# SCH_06_Analog_Mux.net
KiCad netlist of a schematic drawn in Altium Designer
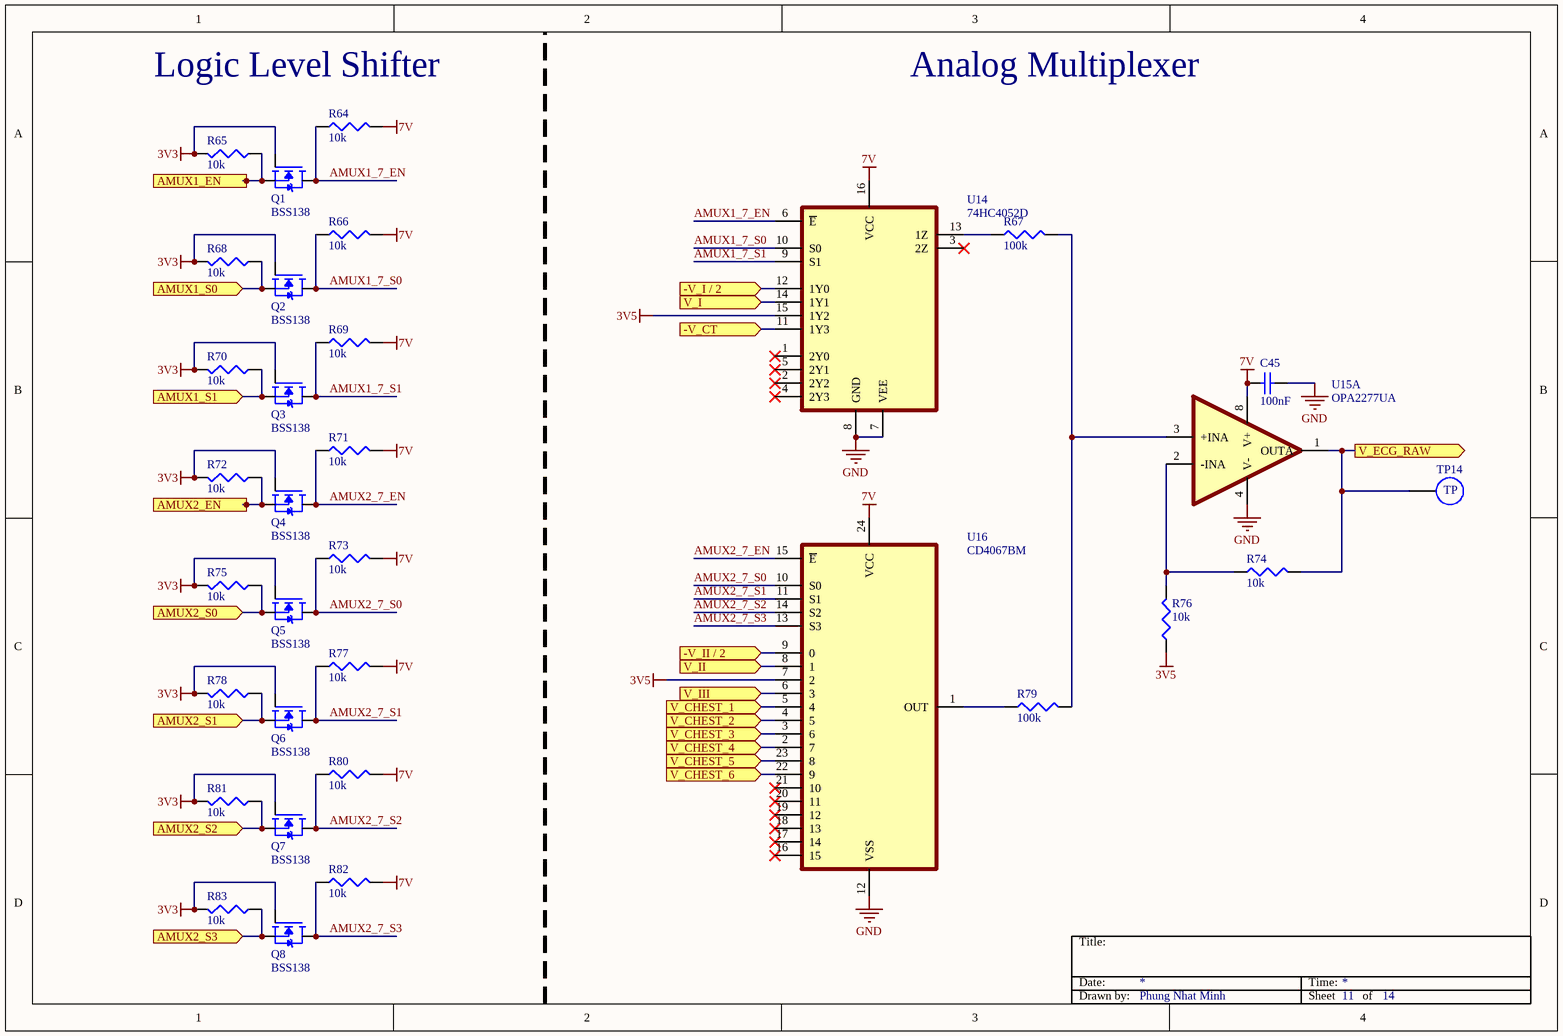
[diagram p0: SCH_06_Analog_Mux.SchDoc]

(export (version "E")
  (design (tool "Eeschema 10.0.6"))
  (components
    (comp (ref "C45")
      (value "100nF")
      (footprint "WCAP-CSGP_0603_L1.6W0.8H0.8_Reflow")
      (description "WCAP-CSGP Multilayer Ceramic Chip Capacitor, General Purpose, size 0603, X7R, 100nF, 50VDC")
      (fields
        (field (name "MANUFACTURER PART NUMBER") "885012206095")
        (field (name "MANUFACTURER") "Wurth Elektronik")
      )
      (libsource (lib "Altium_WCAP-CSGP (rev24b)") (part "885012206095"))
    )
    (comp (ref "Q1")
      (value "BSS138")
      (footprint "SOT95P240X111-3N")
      (description "N-Channel 50V 220mA (Ta) 360mW (Ta) Surface Mount SOT-23-3")
      (fields (field (name "MF") "ON Semiconductor"))
      (libsource (lib "BSS138") (part "BSS138"))
    )
    (comp (ref "Q2")
      (value "BSS138")
      (footprint "SOT95P240X111-3N")
      (description "N-Channel 50V 220mA (Ta) 360mW (Ta) Surface Mount SOT-23-3")
      (fields (field (name "MF") "ON Semiconductor"))
      (libsource (lib "BSS138") (part "BSS138"))
    )
    (comp (ref "Q3")
      (value "BSS138")
      (footprint "SOT95P240X111-3N")
      (description "N-Channel 50V 220mA (Ta) 360mW (Ta) Surface Mount SOT-23-3")
      (fields (field (name "MF") "ON Semiconductor"))
      (libsource (lib "BSS138") (part "BSS138"))
    )
    (comp (ref "Q4")
      (value "BSS138")
      (footprint "SOT95P240X111-3N")
      (description "N-Channel 50V 220mA (Ta) 360mW (Ta) Surface Mount SOT-23-3")
      (fields (field (name "MF") "ON Semiconductor"))
      (libsource (lib "BSS138") (part "BSS138"))
    )
    (comp (ref "Q5")
      (value "BSS138")
      (footprint "SOT95P240X111-3N")
      (description "N-Channel 50V 220mA (Ta) 360mW (Ta) Surface Mount SOT-23-3")
      (fields (field (name "MF") "ON Semiconductor"))
      (libsource (lib "BSS138") (part "BSS138"))
    )
    (comp (ref "Q6")
      (value "BSS138")
      (footprint "SOT95P240X111-3N")
      (description "N-Channel 50V 220mA (Ta) 360mW (Ta) Surface Mount SOT-23-3")
      (fields (field (name "MF") "ON Semiconductor"))
      (libsource (lib "BSS138") (part "BSS138"))
    )
    (comp (ref "Q7")
      (value "BSS138")
      (footprint "SOT95P240X111-3N")
      (description "N-Channel 50V 220mA (Ta) 360mW (Ta) Surface Mount SOT-23-3")
      (fields (field (name "MF") "ON Semiconductor"))
      (libsource (lib "BSS138") (part "BSS138"))
    )
    (comp (ref "Q8")
      (value "BSS138")
      (footprint "SOT95P240X111-3N")
      (description "N-Channel 50V 220mA (Ta) 360mW (Ta) Surface Mount SOT-23-3")
      (fields (field (name "MF") "ON Semiconductor"))
      (libsource (lib "BSS138") (part "BSS138"))
    )
    (comp (ref "R64")
      (value "10k")
      (footprint "WRIS-PSMB_0603_L1.6W0.8H0.35")
      (description "WRIS-PSMB Metal Plate Resistor, SMT, size 0603, 0.33W, 5mΩ, +/-1%")
      (fields
        (field (name "MANUFACTURER PART NUMBER") "580060716001")
        (field (name "MANUFACTURER") "Wurth Elektronik")
      )
      (libsource (lib "Altium_WRIS-PSMB (rev22a)") (part "580060716001"))
    )
    (comp (ref "R65")
      (value "10k")
      (footprint "WRIS-PSMB_0603_L1.6W0.8H0.35")
      (description "WRIS-PSMB Metal Plate Resistor, SMT, size 0603, 0.33W, 5mΩ, +/-1%")
      (fields
        (field (name "MANUFACTURER PART NUMBER") "580060716001")
        (field (name "MANUFACTURER") "Wurth Elektronik")
      )
      (libsource (lib "Altium_WRIS-PSMB (rev22a)") (part "580060716001"))
    )
    (comp (ref "R66")
      (value "10k")
      (footprint "WRIS-PSMB_0603_L1.6W0.8H0.35")
      (description "WRIS-PSMB Metal Plate Resistor, SMT, size 0603, 0.33W, 5mΩ, +/-1%")
      (fields
        (field (name "MANUFACTURER PART NUMBER") "580060716001")
        (field (name "MANUFACTURER") "Wurth Elektronik")
      )
      (libsource (lib "Altium_WRIS-PSMB (rev22a)") (part "580060716001"))
    )
    (comp (ref "R67")
      (value "100k")
      (footprint "WRIS-PSMB_0603_L1.6W0.8H0.35")
      (description "WRIS-PSMB Metal Plate Resistor, SMT, size 0603, 0.33W, 5mΩ, +/-1%")
      (fields
        (field (name "MANUFACTURER PART NUMBER") "580060716001")
        (field (name "MANUFACTURER") "Wurth Elektronik")
      )
      (libsource (lib "Altium_WRIS-PSMB (rev22a)") (part "580060716001"))
    )
    (comp (ref "R68")
      (value "10k")
      (footprint "WRIS-PSMB_0603_L1.6W0.8H0.35")
      (description "WRIS-PSMB Metal Plate Resistor, SMT, size 0603, 0.33W, 5mΩ, +/-1%")
      (fields
        (field (name "MANUFACTURER PART NUMBER") "580060716001")
        (field (name "MANUFACTURER") "Wurth Elektronik")
      )
      (libsource (lib "Altium_WRIS-PSMB (rev22a)") (part "580060716001"))
    )
    (comp (ref "R69")
      (value "10k")
      (footprint "WRIS-PSMB_0603_L1.6W0.8H0.35")
      (description "WRIS-PSMB Metal Plate Resistor, SMT, size 0603, 0.33W, 5mΩ, +/-1%")
      (fields
        (field (name "MANUFACTURER PART NUMBER") "580060716001")
        (field (name "MANUFACTURER") "Wurth Elektronik")
      )
      (libsource (lib "Altium_WRIS-PSMB (rev22a)") (part "580060716001"))
    )
    (comp (ref "R70")
      (value "10k")
      (footprint "WRIS-PSMB_0603_L1.6W0.8H0.35")
      (description "WRIS-PSMB Metal Plate Resistor, SMT, size 0603, 0.33W, 5mΩ, +/-1%")
      (fields
        (field (name "MANUFACTURER PART NUMBER") "580060716001")
        (field (name "MANUFACTURER") "Wurth Elektronik")
      )
      (libsource (lib "Altium_WRIS-PSMB (rev22a)") (part "580060716001"))
    )
    (comp (ref "R71")
      (value "10k")
      (footprint "WRIS-PSMB_0603_L1.6W0.8H0.35")
      (description "WRIS-PSMB Metal Plate Resistor, SMT, size 0603, 0.33W, 5mΩ, +/-1%")
      (fields
        (field (name "MANUFACTURER PART NUMBER") "580060716001")
        (field (name "MANUFACTURER") "Wurth Elektronik")
      )
      (libsource (lib "Altium_WRIS-PSMB (rev22a)") (part "580060716001"))
    )
    (comp (ref "R72")
      (value "10k")
      (footprint "WRIS-PSMB_0603_L1.6W0.8H0.35")
      (description "WRIS-PSMB Metal Plate Resistor, SMT, size 0603, 0.33W, 5mΩ, +/-1%")
      (fields
        (field (name "MANUFACTURER PART NUMBER") "580060716001")
        (field (name "MANUFACTURER") "Wurth Elektronik")
      )
      (libsource (lib "Altium_WRIS-PSMB (rev22a)") (part "580060716001"))
    )
    (comp (ref "R73")
      (value "10k")
      (footprint "WRIS-PSMB_0603_L1.6W0.8H0.35")
      (description "WRIS-PSMB Metal Plate Resistor, SMT, size 0603, 0.33W, 5mΩ, +/-1%")
      (fields
        (field (name "MANUFACTURER PART NUMBER") "580060716001")
        (field (name "MANUFACTURER") "Wurth Elektronik")
      )
      (libsource (lib "Altium_WRIS-PSMB (rev22a)") (part "580060716001"))
    )
    (comp (ref "R74")
      (value "10k")
      (footprint "WRIS-PSMB_0603_L1.6W0.8H0.35")
      (description "WRIS-PSMB Metal Plate Resistor, SMT, size 0603, 0.33W, 5mΩ, +/-1%")
      (fields
        (field (name "MANUFACTURER PART NUMBER") "580060716001")
        (field (name "MANUFACTURER") "Wurth Elektronik")
      )
      (libsource (lib "Altium_WRIS-PSMB (rev22a)") (part "580060716001"))
    )
    (comp (ref "R75")
      (value "10k")
      (footprint "WRIS-PSMB_0603_L1.6W0.8H0.35")
      (description "WRIS-PSMB Metal Plate Resistor, SMT, size 0603, 0.33W, 5mΩ, +/-1%")
      (fields
        (field (name "MANUFACTURER PART NUMBER") "580060716001")
        (field (name "MANUFACTURER") "Wurth Elektronik")
      )
      (libsource (lib "Altium_WRIS-PSMB (rev22a)") (part "580060716001"))
    )
    (comp (ref "R76")
      (value "10k")
      (footprint "WRIS-PSMB_0603_L1.6W0.8H0.35")
      (description "WRIS-PSMB Metal Plate Resistor, SMT, size 0603, 0.33W, 5mΩ, +/-1%")
      (fields
        (field (name "MANUFACTURER PART NUMBER") "580060716001")
        (field (name "MANUFACTURER") "Wurth Elektronik")
      )
      (libsource (lib "Altium_WRIS-PSMB (rev22a)") (part "580060716001"))
    )
    (comp (ref "R77")
      (value "10k")
      (footprint "WRIS-PSMB_0603_L1.6W0.8H0.35")
      (description "WRIS-PSMB Metal Plate Resistor, SMT, size 0603, 0.33W, 5mΩ, +/-1%")
      (fields
        (field (name "MANUFACTURER PART NUMBER") "580060716001")
        (field (name "MANUFACTURER") "Wurth Elektronik")
      )
      (libsource (lib "Altium_WRIS-PSMB (rev22a)") (part "580060716001"))
    )
    (comp (ref "R78")
      (value "10k")
      (footprint "WRIS-PSMB_0603_L1.6W0.8H0.35")
      (description "WRIS-PSMB Metal Plate Resistor, SMT, size 0603, 0.33W, 5mΩ, +/-1%")
      (fields
        (field (name "MANUFACTURER PART NUMBER") "580060716001")
        (field (name "MANUFACTURER") "Wurth Elektronik")
      )
      (libsource (lib "Altium_WRIS-PSMB (rev22a)") (part "580060716001"))
    )
    (comp (ref "R79")
      (value "100k")
      (footprint "WRIS-PSMB_0603_L1.6W0.8H0.35")
      (description "WRIS-PSMB Metal Plate Resistor, SMT, size 0603, 0.33W, 5mΩ, +/-1%")
      (fields
        (field (name "MANUFACTURER PART NUMBER") "580060716001")
        (field (name "MANUFACTURER") "Wurth Elektronik")
      )
      (libsource (lib "Altium_WRIS-PSMB (rev22a)") (part "580060716001"))
    )
    (comp (ref "R80")
      (value "10k")
      (footprint "WRIS-PSMB_0603_L1.6W0.8H0.35")
      (description "WRIS-PSMB Metal Plate Resistor, SMT, size 0603, 0.33W, 5mΩ, +/-1%")
      (fields
        (field (name "MANUFACTURER PART NUMBER") "580060716001")
        (field (name "MANUFACTURER") "Wurth Elektronik")
      )
      (libsource (lib "Altium_WRIS-PSMB (rev22a)") (part "580060716001"))
    )
    (comp (ref "R81")
      (value "10k")
      (footprint "WRIS-PSMB_0603_L1.6W0.8H0.35")
      (description "WRIS-PSMB Metal Plate Resistor, SMT, size 0603, 0.33W, 5mΩ, +/-1%")
      (fields
        (field (name "MANUFACTURER PART NUMBER") "580060716001")
        (field (name "MANUFACTURER") "Wurth Elektronik")
      )
      (libsource (lib "Altium_WRIS-PSMB (rev22a)") (part "580060716001"))
    )
    (comp (ref "R82")
      (value "10k")
      (footprint "WRIS-PSMB_0603_L1.6W0.8H0.35")
      (description "WRIS-PSMB Metal Plate Resistor, SMT, size 0603, 0.33W, 5mΩ, +/-1%")
      (fields
        (field (name "MANUFACTURER PART NUMBER") "580060716001")
        (field (name "MANUFACTURER") "Wurth Elektronik")
      )
      (libsource (lib "Altium_WRIS-PSMB (rev22a)") (part "580060716001"))
    )
    (comp (ref "R83")
      (value "10k")
      (footprint "WRIS-PSMB_0603_L1.6W0.8H0.35")
      (description "WRIS-PSMB Metal Plate Resistor, SMT, size 0603, 0.33W, 5mΩ, +/-1%")
      (fields
        (field (name "MANUFACTURER PART NUMBER") "580060716001")
        (field (name "MANUFACTURER") "Wurth Elektronik")
      )
      (libsource (lib "Altium_WRIS-PSMB (rev22a)") (part "580060716001"))
    )
    (comp (ref "TP14")
      (value "Pad_Test_Point")
      (footprint "Pad_Test_Point")
      (libsource (lib "Test_Point") (part "Pad_Test_Point"))
    )
    (comp (ref "U14")
      (value "74HC4052D")
      (footprint "SOIC127P600X175-16N")
      (description "2 Circuit IC Switch 4:1 150Ohm 16-SO")
      (fields (field (name "MP") "74HC4052D,653") (field (name "MF") "Nexperia USA"))
      (libsource (lib "74HC4052D_653") (part "74HC4052D"))
    )
    (comp (ref "U15")
      (value "OPA2277UA")
      (footprint "SOIC127P599X175-8N")
      (fields (field (name "MP") "OPA2227UA"))
      (libsource (lib "OPA2277") (part "OPA2277UA"))
    )
    (comp (ref "U16")
      (value "CD4067BM")
      (footprint "SOIC127P1030X265-24N")
      (libsource (lib "CD4067BM") (part "CD4067BM"))
    )
  )
  (nets
    (net (code "1") (name "/-V_CT") (class "Default")
      (node (ref "U14") (pin "11") (pinfunction "1Y3_11") (pintype "passive"))
    )
    (net (code "2") (name "/-V_I {slash} 2") (class "Default")
      (node (ref "U14") (pin "12") (pinfunction "1Y0_12") (pintype "passive"))
    )
    (net (code "3") (name "/-V_II {slash} 2") (class "Default")
      (node (ref "U16") (pin "9") (pinfunction "0_9") (pintype "passive"))
    )
    (net (code "4") (name "/AMUX1_7_EN") (class "Default")
      (node (ref "Q1") (pin "3") (pinfunction "D_3") (pintype "passive"))
      (node (ref "R64") (pin "1") (pinfunction "1_1") (pintype "passive"))
      (node (ref "U14") (pin "6") (pinfunction "~{E}_6") (pintype "passive"))
    )
    (net (code "5") (name "/AMUX1_7_S0") (class "Default")
      (node (ref "Q2") (pin "3") (pinfunction "D_3") (pintype "passive"))
      (node (ref "R66") (pin "1") (pinfunction "1_1") (pintype "passive"))
      (node (ref "U14") (pin "10") (pinfunction "S0_10") (pintype "passive"))
    )
    (net (code "6") (name "/AMUX1_7_S1") (class "Default")
      (node (ref "Q3") (pin "3") (pinfunction "D_3") (pintype "passive"))
      (node (ref "R69") (pin "1") (pinfunction "1_1") (pintype "passive"))
      (node (ref "U14") (pin "9") (pinfunction "S1_9") (pintype "passive"))
    )
    (net (code "7") (name "/AMUX1_EN") (class "Default")
      (node (ref "Q1") (pin "2") (pinfunction "S_2") (pintype "passive"))
      (node (ref "R65") (pin "1") (pinfunction "1_1") (pintype "passive"))
    )
    (net (code "8") (name "/AMUX1_S0") (class "Default")
      (node (ref "Q2") (pin "2") (pinfunction "S_2") (pintype "passive"))
      (node (ref "R68") (pin "1") (pinfunction "1_1") (pintype "passive"))
    )
    (net (code "9") (name "/AMUX1_S1") (class "Default")
      (node (ref "Q3") (pin "2") (pinfunction "S_2") (pintype "passive"))
      (node (ref "R70") (pin "1") (pinfunction "1_1") (pintype "passive"))
    )
    (net (code "10") (name "/AMUX2_7_EN") (class "Default")
      (node (ref "Q4") (pin "3") (pinfunction "D_3") (pintype "passive"))
      (node (ref "R71") (pin "1") (pinfunction "1_1") (pintype "passive"))
      (node (ref "U16") (pin "15") (pinfunction "~{E}_15") (pintype "passive"))
    )
    (net (code "11") (name "/AMUX2_7_S0") (class "Default")
      (node (ref "Q5") (pin "3") (pinfunction "D_3") (pintype "passive"))
      (node (ref "R73") (pin "1") (pinfunction "1_1") (pintype "passive"))
      (node (ref "U16") (pin "10") (pinfunction "S0_10") (pintype "passive"))
    )
    (net (code "12") (name "/AMUX2_7_S1") (class "Default")
      (node (ref "Q6") (pin "3") (pinfunction "D_3") (pintype "passive"))
      (node (ref "R77") (pin "1") (pinfunction "1_1") (pintype "passive"))
      (node (ref "U16") (pin "11") (pinfunction "S1_11") (pintype "passive"))
    )
    (net (code "13") (name "/AMUX2_7_S2") (class "Default")
      (node (ref "Q7") (pin "3") (pinfunction "D_3") (pintype "passive"))
      (node (ref "R80") (pin "1") (pinfunction "1_1") (pintype "passive"))
      (node (ref "U16") (pin "14") (pinfunction "S2_14") (pintype "passive"))
    )
    (net (code "14") (name "/AMUX2_7_S3") (class "Default")
      (node (ref "Q8") (pin "3") (pinfunction "D_3") (pintype "passive"))
      (node (ref "R82") (pin "1") (pinfunction "1_1") (pintype "passive"))
      (node (ref "U16") (pin "13") (pinfunction "S3_13") (pintype "passive"))
    )
    (net (code "15") (name "/AMUX2_EN") (class "Default")
      (node (ref "Q4") (pin "2") (pinfunction "S_2") (pintype "passive"))
      (node (ref "R72") (pin "1") (pinfunction "1_1") (pintype "passive"))
    )
    (net (code "16") (name "/AMUX2_S0") (class "Default")
      (node (ref "Q5") (pin "2") (pinfunction "S_2") (pintype "passive"))
      (node (ref "R75") (pin "1") (pinfunction "1_1") (pintype "passive"))
    )
    (net (code "17") (name "/AMUX2_S1") (class "Default")
      (node (ref "Q6") (pin "2") (pinfunction "S_2") (pintype "passive"))
      (node (ref "R78") (pin "1") (pinfunction "1_1") (pintype "passive"))
    )
    (net (code "18") (name "/AMUX2_S2") (class "Default")
      (node (ref "Q7") (pin "2") (pinfunction "S_2") (pintype "passive"))
      (node (ref "R81") (pin "1") (pinfunction "1_1") (pintype "passive"))
    )
    (net (code "19") (name "/AMUX2_S3") (class "Default")
      (node (ref "Q8") (pin "2") (pinfunction "S_2") (pintype "passive"))
      (node (ref "R83") (pin "1") (pinfunction "1_1") (pintype "passive"))
    )
    (net (code "20") (name "/V_CHEST_1") (class "Default")
      (node (ref "U16") (pin "5") (pinfunction "4_5") (pintype "passive"))
    )
    (net (code "21") (name "/V_CHEST_2") (class "Default")
      (node (ref "U16") (pin "4") (pinfunction "5_4") (pintype "passive"))
    )
    (net (code "22") (name "/V_CHEST_3") (class "Default")
      (node (ref "U16") (pin "3") (pinfunction "6_3") (pintype "passive"))
    )
    (net (code "23") (name "/V_CHEST_4") (class "Default")
      (node (ref "U16") (pin "2") (pinfunction "7_2") (pintype "passive"))
    )
    (net (code "24") (name "/V_CHEST_5") (class "Default")
      (node (ref "U16") (pin "23") (pinfunction "8_23") (pintype "passive"))
    )
    (net (code "25") (name "/V_CHEST_6") (class "Default")
      (node (ref "U16") (pin "22") (pinfunction "9_22") (pintype "passive"))
    )
    (net (code "26") (name "/V_ECG_RAW") (class "Default")
      (node (ref "R74") (pin "2") (pinfunction "2_2") (pintype "passive"))
      (node (ref "TP14") (pin "1") (pinfunction "1_1") (pintype "passive"))
      (node (ref "U15") (pin "1") (pinfunction "OUTA_1") (pintype "passive"))
    )
    (net (code "27") (name "/V_I") (class "Default")
      (node (ref "U14") (pin "14") (pinfunction "1Y1_14") (pintype "passive"))
    )
    (net (code "28") (name "/V_II") (class "Default")
      (node (ref "U16") (pin "8") (pinfunction "1_8") (pintype "passive"))
    )
    (net (code "29") (name "/V_III") (class "Default")
      (node (ref "U16") (pin "6") (pinfunction "3_6") (pintype "passive"))
    )
    (net (code "30") (name "3V3") (class "Default")
      (node (ref "Q1") (pin "1") (pinfunction "G_1") (pintype "passive"))
      (node (ref "Q2") (pin "1") (pinfunction "G_1") (pintype "passive"))
      (node (ref "Q3") (pin "1") (pinfunction "G_1") (pintype "passive"))
      (node (ref "Q4") (pin "1") (pinfunction "G_1") (pintype "passive"))
      (node (ref "Q5") (pin "1") (pinfunction "G_1") (pintype "passive"))
      (node (ref "Q6") (pin "1") (pinfunction "G_1") (pintype "passive"))
      (node (ref "Q7") (pin "1") (pinfunction "G_1") (pintype "passive"))
      (node (ref "Q8") (pin "1") (pinfunction "G_1") (pintype "passive"))
      (node (ref "R65") (pin "2") (pinfunction "2_2") (pintype "passive"))
      (node (ref "R68") (pin "2") (pinfunction "2_2") (pintype "passive"))
      (node (ref "R70") (pin "2") (pinfunction "2_2") (pintype "passive"))
      (node (ref "R72") (pin "2") (pinfunction "2_2") (pintype "passive"))
      (node (ref "R75") (pin "2") (pinfunction "2_2") (pintype "passive"))
      (node (ref "R78") (pin "2") (pinfunction "2_2") (pintype "passive"))
      (node (ref "R81") (pin "2") (pinfunction "2_2") (pintype "passive"))
      (node (ref "R83") (pin "2") (pinfunction "2_2") (pintype "passive"))
    )
    (net (code "31") (name "3V5") (class "Default")
      (node (ref "R76") (pin "1") (pinfunction "1_1") (pintype "passive"))
      (node (ref "U14") (pin "15") (pinfunction "1Y2_15") (pintype "passive"))
      (node (ref "U16") (pin "7") (pinfunction "2_7") (pintype "passive"))
    )
    (net (code "32") (name "7V") (class "Default")
      (node (ref "C45") (pin "2") (pinfunction "2_2") (pintype "passive"))
      (node (ref "R64") (pin "2") (pinfunction "2_2") (pintype "passive"))
      (node (ref "R66") (pin "2") (pinfunction "2_2") (pintype "passive"))
      (node (ref "R69") (pin "2") (pinfunction "2_2") (pintype "passive"))
      (node (ref "R71") (pin "2") (pinfunction "2_2") (pintype "passive"))
      (node (ref "R73") (pin "2") (pinfunction "2_2") (pintype "passive"))
      (node (ref "R77") (pin "2") (pinfunction "2_2") (pintype "passive"))
      (node (ref "R80") (pin "2") (pinfunction "2_2") (pintype "passive"))
      (node (ref "R82") (pin "2") (pinfunction "2_2") (pintype "passive"))
      (node (ref "U14") (pin "16") (pinfunction "VCC_16") (pintype "power_in"))
      (node (ref "U15") (pin "8") (pinfunction "V+_8") (pintype "power_in"))
      (node (ref "U16") (pin "24") (pinfunction "VCC_24") (pintype "power_in"))
    )
    (net (code "33") (name "GND") (class "Default")
      (node (ref "C45") (pin "1") (pinfunction "1_1") (pintype "passive"))
      (node (ref "U14") (pin "7") (pinfunction "VEE_7") (pintype "power_in"))
      (node (ref "U14") (pin "8") (pinfunction "GND_8") (pintype "power_in"))
      (node (ref "U15") (pin "4") (pinfunction "V-_4") (pintype "power_in"))
      (node (ref "U16") (pin "12") (pinfunction "VSS_12") (pintype "power_in"))
    )
    (net (code "34") (name "Net-(U14-1Z)") (class "Default")
      (node (ref "R67") (pin "1") (pinfunction "1_1") (pintype "passive"))
      (node (ref "U14") (pin "13") (pinfunction "1Z_13") (pintype "passive"))
    )
    (net (code "35") (name "Net-(U15A-+INA)") (class "Default")
      (node (ref "R67") (pin "2") (pinfunction "2_2") (pintype "passive"))
      (node (ref "R79") (pin "2") (pinfunction "2_2") (pintype "passive"))
      (node (ref "U15") (pin "3") (pinfunction "+INA_3") (pintype "passive"))
    )
    (net (code "36") (name "Net-(U15A--INA)") (class "Default")
      (node (ref "R74") (pin "1") (pinfunction "1_1") (pintype "passive"))
      (node (ref "R76") (pin "2") (pinfunction "2_2") (pintype "passive"))
      (node (ref "U15") (pin "2") (pinfunction "-INA_2") (pintype "passive"))
    )
    (net (code "37") (name "Net-(U16-OUT)") (class "Default")
      (node (ref "R79") (pin "1") (pinfunction "1_1") (pintype "passive"))
      (node (ref "U16") (pin "1") (pinfunction "OUT_1") (pintype "passive"))
    )
    (net (code "38") (name "unconnected-(U14-2Y0-Pad1)") (class "Default")
      (node (ref "U14") (pin "1") (pinfunction "2Y0_1") (pintype "passive+no_connect"))
    )
    (net (code "39") (name "unconnected-(U14-2Y1-Pad5)") (class "Default")
      (node (ref "U14") (pin "5") (pinfunction "2Y1_5") (pintype "passive+no_connect"))
    )
    (net (code "40") (name "unconnected-(U14-2Y2-Pad2)") (class "Default")
      (node (ref "U14") (pin "2") (pinfunction "2Y2_2") (pintype "passive+no_connect"))
    )
    (net (code "41") (name "unconnected-(U14-2Y3-Pad4)") (class "Default")
      (node (ref "U14") (pin "4") (pinfunction "2Y3_4") (pintype "passive+no_connect"))
    )
    (net (code "42") (name "unconnected-(U14-2Z-Pad3)") (class "Default")
      (node (ref "U14") (pin "3") (pinfunction "2Z_3") (pintype "passive+no_connect"))
    )
    (net (code "43") (name "unconnected-(U16-10-Pad21)") (class "Default")
      (node (ref "U16") (pin "21") (pinfunction "10_21") (pintype "passive+no_connect"))
    )
    (net (code "44") (name "unconnected-(U16-11-Pad20)") (class "Default")
      (node (ref "U16") (pin "20") (pinfunction "11_20") (pintype "passive+no_connect"))
    )
    (net (code "45") (name "unconnected-(U16-12-Pad19)") (class "Default")
      (node (ref "U16") (pin "19") (pinfunction "12_19") (pintype "passive+no_connect"))
    )
    (net (code "46") (name "unconnected-(U16-13-Pad18)") (class "Default")
      (node (ref "U16") (pin "18") (pinfunction "13_18") (pintype "passive+no_connect"))
    )
    (net (code "47") (name "unconnected-(U16-14-Pad17)") (class "Default")
      (node (ref "U16") (pin "17") (pinfunction "14_17") (pintype "passive+no_connect"))
    )
    (net (code "48") (name "unconnected-(U16-15-Pad16)") (class "Default")
      (node (ref "U16") (pin "16") (pinfunction "15_16") (pintype "passive+no_connect"))
    )
  )
)
